# SCH_NFC-Card_2024-10-10.net
KiCad netlist of a schematic drawn in EasyEDA
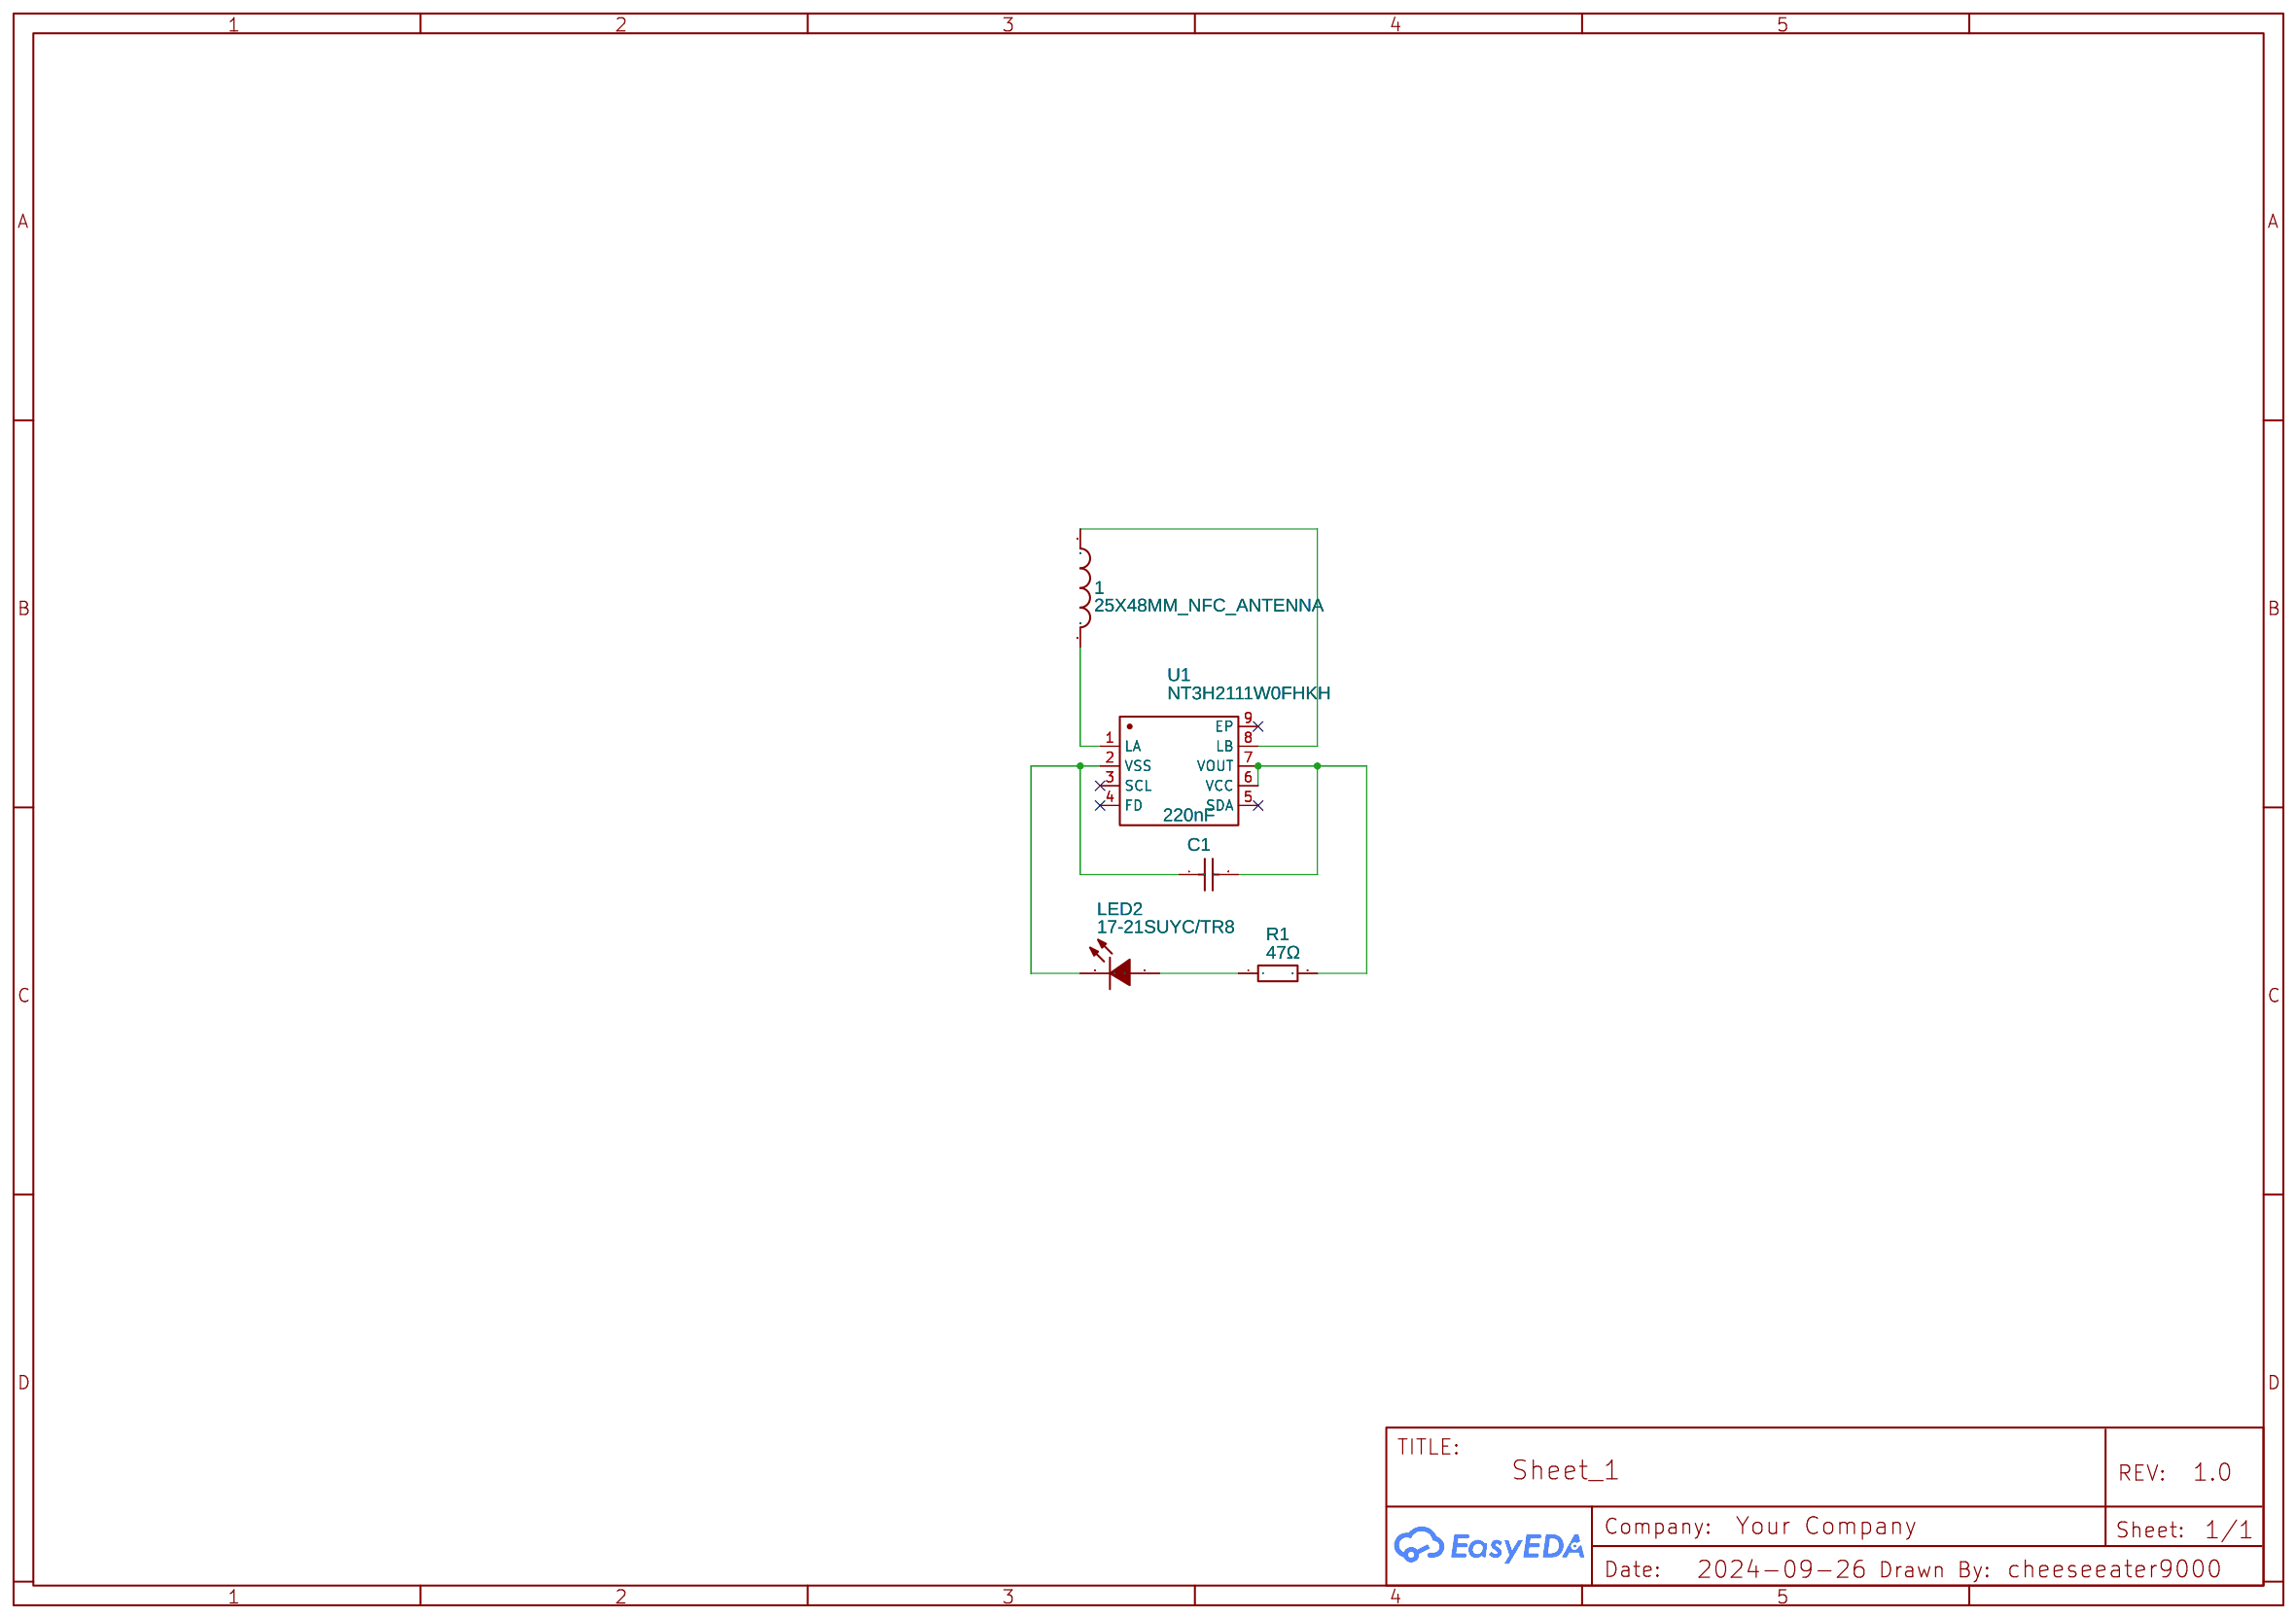
[diagram p0: schematic sheet]

(export (version "E")
  (design (tool "Eeschema 10.0.6"))
  (components
    (comp (ref "1") (value "25X48MM_NFC_ANTENNA") (libsource (lib "") (part "25X48MM_NFC_ANTENNA")))
    (comp (ref "C1")
      (value "220nF")
      (fields
        (field (name "Manufacturer Part") "CL10B224KA8NNNC")
        (field (name "Manufacturer") "SAMSUNG(三星)")
      )
      (libsource (lib "") (part "CL10B224KA8NNNC"))
    )
    (comp (ref "LED2")
      (value "17-21SUYC/TR8")
      (fields (field (name "Manufacturer Part") "KT-0805黄灯") (field (name "Manufacturer") "KENTO"))
      (libsource (lib "") (part "17-21SUYC/TR8"))
    )
    (comp (ref "R1")
      (value "47Ω")
      (fields
        (field (name "Manufacturer Part") "0603WAF470JT5E")
        (field (name "Manufacturer") "UNI-ROYAL(厚声)")
      )
      (libsource (lib "") (part "0603WAF470JT5E"))
    )
    (comp (ref "U1")
      (value "NT3H2111W0FHKH")
      (fields (field (name "Manufacturer") "NXP(恩智浦)"))
      (libsource (lib "") (part "NT3H2111W0FHKH"))
    )
  )
  (nets
    (net (code "1") (name "Net-(LED2-+)") (class "Default")
      (node (ref "LED2") (pin "1") (pinfunction "+_1") (pintype "unspecified"))
      (node (ref "R1") (pin "1") (pinfunction "1_1") (pintype "input"))
    )
    (net (code "2") (name "Net-(LED2--)") (class "Default")
      (node (ref "C1") (pin "1") (pinfunction "1_1") (pintype "input"))
      (node (ref "LED2") (pin "2") (pinfunction "-_2") (pintype "unspecified"))
      (node (ref "U1") (pin "2") (pinfunction "VSS_2") (pintype "unspecified"))
    )
    (net (code "3") (name "Net-(U1-LA)") (class "Default")
      (node (ref "1") (pin "P$2") (pinfunction "P$2_P$2") (pintype "bidirectional"))
      (node (ref "U1") (pin "1") (pinfunction "LA_1") (pintype "unspecified"))
    )
    (net (code "4") (name "Net-(U1-LB)") (class "Default")
      (node (ref "1") (pin "P$1") (pinfunction "P$1_P$1") (pintype "bidirectional"))
      (node (ref "U1") (pin "8") (pinfunction "LB_8") (pintype "unspecified"))
    )
    (net (code "5") (name "Net-(U1-VCC)") (class "Default")
      (node (ref "C1") (pin "2") (pinfunction "2_2") (pintype "input"))
      (node (ref "R1") (pin "2") (pinfunction "2_2") (pintype "input"))
      (node (ref "U1") (pin "6") (pinfunction "VCC_6") (pintype "unspecified"))
      (node (ref "U1") (pin "7") (pinfunction "VOUT_7") (pintype "unspecified"))
    )
    (net (code "6") (name "unconnected-(U1-EP-Pad9)") (class "Default")
      (node (ref "U1") (pin "9") (pinfunction "EP_9") (pintype "unspecified+no_connect"))
    )
    (net (code "7") (name "unconnected-(U1-FD-Pad4)") (class "Default")
      (node (ref "U1") (pin "4") (pinfunction "FD_4") (pintype "unspecified+no_connect"))
    )
    (net (code "8") (name "unconnected-(U1-SCL-Pad3)") (class "Default")
      (node (ref "U1") (pin "3") (pinfunction "SCL_3") (pintype "unspecified+no_connect"))
    )
    (net (code "9") (name "unconnected-(U1-SDA-Pad5)") (class "Default")
      (node (ref "U1") (pin "5") (pinfunction "SDA_5") (pintype "unspecified+no_connect"))
    )
  )
)
